# 07_-SOLENOID.net
KiCad netlist of a schematic drawn in Altium Designer
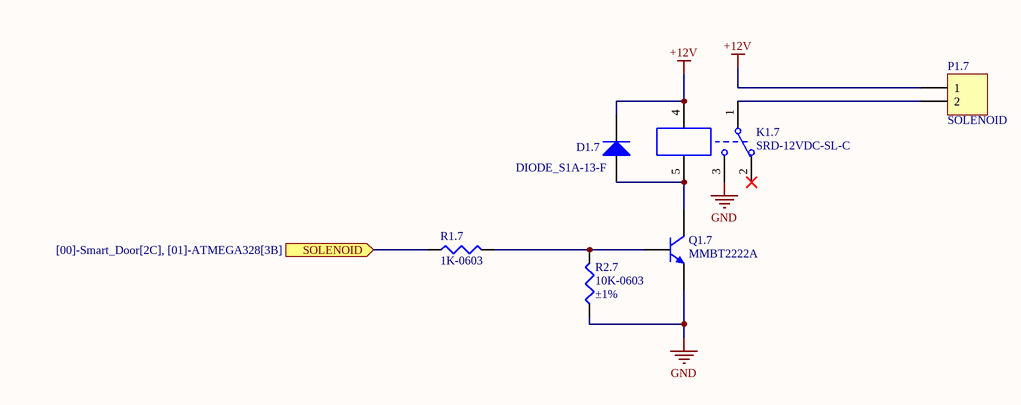
[diagram p0: [07]-SOLENOID.SchDoc]

(export (version "E")
  (design (tool "Eeschema 10.0.6"))
  (components
    (comp (ref "D1.7")
      (value "DIODE_S1A-13-F")
      (footprint "DO-214AC")
      (description "DIODE GEN PURP 50V 1A SMA")
      (fields
        (field (name "MANUFACTURER") "Diodes Incorporated")
        (field (name "MANUFACTURER PART NUMBER") "S1A-13-F")
      )
      (libsource (lib "Indruino") (part "DIODE_S1A-13-F"))
    )
    (comp (ref "K1.7")
      (value "SRD-12VDC-SL-C")
      (footprint "MinhTien_PCBLib:RELAY5PIN-10A")
      (fields (field (name "PUBLISHER") "Altium Limited"))
      (libsource (lib "MinhTien_SCHLib") (part "Relay-SRD-05VDC-SL-C"))
    )
    (comp (ref "P1.7")
      (value "SOLENOID")
      (footprint "MinhTien_PCBLib:DOMINO_2PIN_3.81MM_RUT")
      (libsource (lib "MinhTien_SCHLib") (part "Domino 2 pin"))
    )
    (comp (ref "Q1.7")
      (value "MMBT2222A")
      (footprint "Indruino:SOT23-3")
      (description "TRANS NPN 40V 1A SOT-23")
      (fields (field (name "MANUFACTURER") "ON Semiconductor") (field (name "BASE PART NUMBER") "MMBT2222"))
      (libsource (lib "Indruino") (part "MMBT2222A"))
    )
    (comp (ref "R1.7")
      (value "1K-0603")
      (footprint "RES0603")
      (description "RES SMD 1K OHM 5% 1/10W 0603")
      (fields (field (name "TOLERANCE") "±5%"))
      (libsource (lib "Indruino") (part "RC0603JR-071KL"))
    )
    (comp (ref "R2.7")
      (value "10K-0603")
      (footprint "RES0603")
      (description "RES SMD 10K OHM 1% 1/10W 0603")
      (fields
        (field (name "MANUFACTURER") "Yageo")
        (field (name "MANUFACTURER PART NUMBER") "RC0603FR-0710KL")
        (field (name "TOLERANCE") "±1%")
      )
      (libsource (lib "Indruino") (part "RC0603FR-0710KL"))
    )
  )
  (nets
    (net (code "1") (name "+12V") (class "Default")
      (node (ref "D1.7") (pin "2") (pinfunction "K_2") (pintype "passive"))
      (node (ref "K1.7") (pin "4") (pintype "passive"))
      (node (ref "P1.7") (pin "1") (pinfunction "1_1") (pintype "passive"))
    )
    (net (code "2") (name "/SOLENOID") (class "Default")
      (node (ref "R1.7") (pin "1") (pinfunction "1_1") (pintype "passive"))
    )
    (net (code "3") (name "GND") (class "Default")
      (node (ref "K1.7") (pin "3") (pinfunction "NO_3") (pintype "passive"))
      (node (ref "Q1.7") (pin "2") (pinfunction "E_2") (pintype "passive"))
      (node (ref "R2.7") (pin "1") (pinfunction "1_1") (pintype "passive"))
    )
    (net (code "4") (name "Net-(D1.7-A)") (class "Default")
      (node (ref "D1.7") (pin "1") (pinfunction "A_1") (pintype "passive"))
      (node (ref "K1.7") (pin "5") (pintype "passive"))
      (node (ref "Q1.7") (pin "3") (pinfunction "C_3") (pintype "passive"))
    )
    (net (code "5") (name "Net-(K1.7-COM)") (class "Default")
      (node (ref "K1.7") (pin "1") (pinfunction "COM_1") (pintype "passive"))
      (node (ref "P1.7") (pin "2") (pinfunction "2_2") (pintype "passive"))
    )
    (net (code "6") (name "Net-(Q1.7-B)") (class "Default")
      (node (ref "Q1.7") (pin "1") (pinfunction "B_1") (pintype "passive"))
      (node (ref "R1.7") (pin "2") (pinfunction "2_2") (pintype "passive"))
      (node (ref "R2.7") (pin "2") (pinfunction "2_2") (pintype "passive"))
    )
    (net (code "7") (name "unconnected-(K1.7-NC-Pad2)") (class "Default")
      (node (ref "K1.7") (pin "2") (pinfunction "NC_2") (pintype "passive+no_connect"))
    )
  )
)
